# Gate_Drivers.net
KiCad netlist of a schematic drawn in Altium Designer
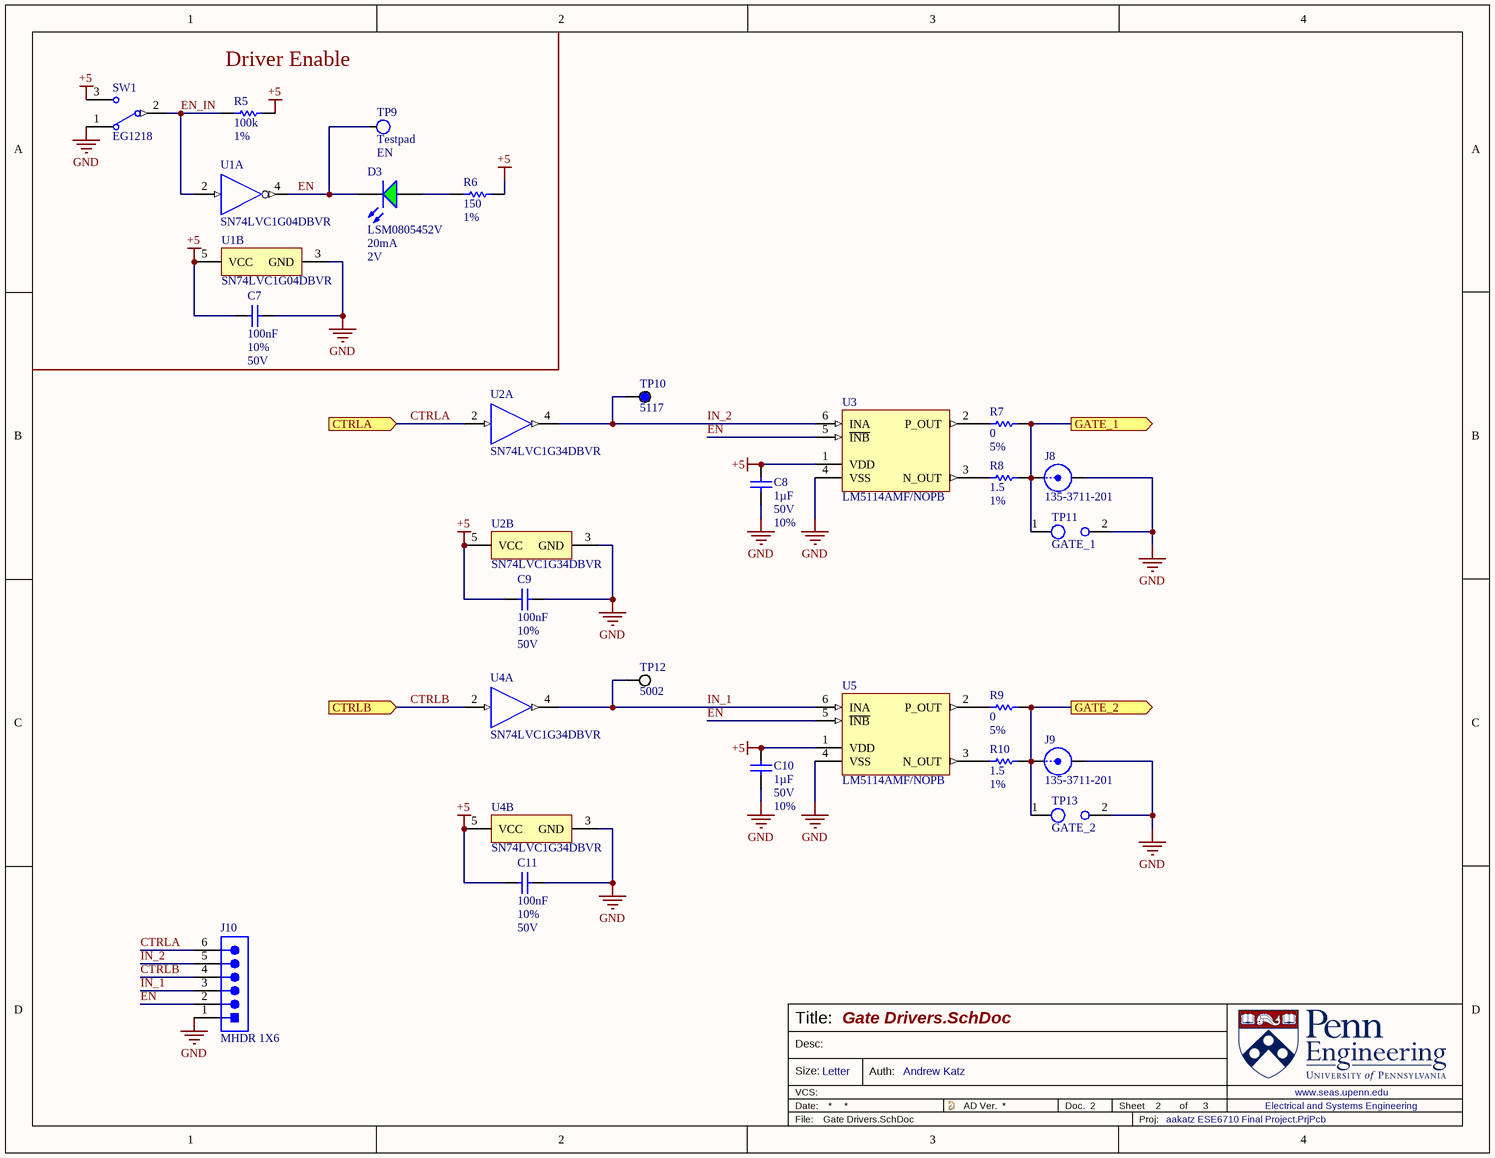
[diagram p0: Gate Drivers.SchDoc]

(export (version "E")
  (design (tool "Eeschema 10.0.6"))
  (components
    (comp (ref "C7")
      (value "100nF")
      (footprint "0805_CAP")
      (description "Capacitor Surface Mount 0805 Footprint 0.1UF 50V 10% Tolerance Ceramic X7R")
      (fields
        (field (name "TOLERANCE") "10%")
        (field (name "MANUFACTURER") "Various")
        (field (name "VOLTAGE") "50V")
        (field (name "Comment") "CAP 0805 0.1UF 50V 10% X7R")
      )
      (libsource (lib "University of Pennsylvania (ESE)") (part "cap"))
    )
    (comp (ref "C8")
      (value "1µF")
      (footprint "1206_CAP")
      (description "Capacitor Surface Mount 1206 Footprint 1.0UF 50V 10% Tolerance Ceramic X7R")
      (fields
        (field (name "VOLTAGE") "50V")
        (field (name "TOLERANCE") "10%")
        (field (name "MANUFACTURER") "Various")
        (field (name "Comment") "CAP 1206 1.0UF 50V 10% X7R")
      )
      (libsource (lib "University of Pennsylvania (ESE)") (part "cap"))
    )
    (comp (ref "C9")
      (value "100nF")
      (footprint "0805_CAP")
      (description "Capacitor Surface Mount 0805 Footprint 0.1UF 50V 10% Tolerance Ceramic X7R")
      (fields
        (field (name "TOLERANCE") "10%")
        (field (name "MANUFACTURER") "Various")
        (field (name "VOLTAGE") "50V")
        (field (name "Comment") "CAP 0805 0.1UF 50V 10% X7R")
      )
      (libsource (lib "University of Pennsylvania (ESE)") (part "cap"))
    )
    (comp (ref "C10")
      (value "1µF")
      (footprint "1206_CAP")
      (description "Capacitor Surface Mount 1206 Footprint 1.0UF 50V 10% Tolerance Ceramic X7R")
      (fields
        (field (name "VOLTAGE") "50V")
        (field (name "TOLERANCE") "10%")
        (field (name "MANUFACTURER") "Various")
        (field (name "Comment") "CAP 1206 1.0UF 50V 10% X7R")
      )
      (libsource (lib "University of Pennsylvania (ESE)") (part "cap"))
    )
    (comp (ref "C11")
      (value "100nF")
      (footprint "0805_CAP")
      (description "Capacitor Surface Mount 0805 Footprint 0.1UF 50V 10% Tolerance Ceramic X7R")
      (fields
        (field (name "TOLERANCE") "10%")
        (field (name "MANUFACTURER") "Various")
        (field (name "VOLTAGE") "50V")
        (field (name "Comment") "CAP 0805 0.1UF 50V 10% X7R")
      )
      (libsource (lib "University of Pennsylvania (ESE)") (part "cap"))
    )
    (comp (ref "D3")
      (value "LSM0805452V")
      (footprint "LED_0805")
      (description "Single Color LED, Green, 0805")
      (fields (field (name "CURRENT") "20mA") (field (name "FORWARD VOLTAGE") "2V"))
      (libsource (lib "University of Pennsylvania (ESE)") (part "LED-GREEN-AK-2"))
    )
    (comp (ref "J8")
      (value "135-3711-201")
      (footprint "135-3711-201-Vias-Footprint-1")
      (description "RF / Coaxial Connector, MMCX Coaxial, Straight Jack, Surface Mount Straight, 50 ohm")
      (libsource (lib "University of Pennsylvania (ESE)") (part "RF Connector"))
    )
    (comp (ref "J9")
      (value "135-3711-201")
      (footprint "135-3711-201-Vias-Footprint-1")
      (description "RF / Coaxial Connector, MMCX Coaxial, Straight Jack, Surface Mount Straight, 50 ohm")
      (libsource (lib "University of Pennsylvania (ESE)") (part "RF Connector"))
    )
    (comp (ref "J10")
      (value "MHDR 1X6")
      (footprint "MHDR 1X6")
      (description "Header, 6-Pin, 0.1in Pitch, Male")
      (fields (field (name "JLCPCB PART #") "C178289"))
      (libsource (lib "University of Pennsylvania (ESE)") (part "Header 1X6"))
    )
    (comp (ref "R5")
      (value "100k")
      (footprint "0805_RES")
      (description "Resistor Surface Mount, 100K Ohms, 0805 Footprint, 1% Tolerance 0.125W")
      (fields
        (field (name "MANUFACTURER") "Various")
        (field (name "TOLERANCE") "1%")
        (field (name "Comment") "RES 0805 100K 1%")
      )
      (libsource (lib "University of Pennsylvania (ESE)") (part "res"))
    )
    (comp (ref "R6")
      (value "150")
      (footprint "0805_RES")
      (description "Resistor Surface Mount, 150 Ohms, 0805 Footprint, 1% Tolerance 0.125W")
      (fields
        (field (name "MANUFACTURER") "Various")
        (field (name "TOLERANCE") "1%")
        (field (name "Comment") "RES 0805 150 1%")
      )
      (libsource (lib "University of Pennsylvania (ESE)") (part "res"))
    )
    (comp (ref "R7")
      (value "0")
      (footprint "0603_RES")
      (description "Resistor Surface Mount, 0 Ohms, 0603 Footprint, 5% Tolerance 0.1W")
      (fields
        (field (name "JLCPCB PART #") "C21189")
        (field (name "TOLERANCE") "5%")
        (field (name "MANUFACTURER") "Various")
      )
      (libsource (lib "University of Pennsylvania (ESE)") (part "res"))
    )
    (comp (ref "R8")
      (value "1.5")
      (footprint "0603_RES")
      (description "Resistor Surface Mount, 1.5 Ohms, 0603 Footprint, 1% Tolerance 0.1W")
      (fields
        (field (name "TOLERANCE") "1%")
        (field (name "MANUFACTURER") "Various")
        (field (name "Comment") "RES 0603 1.5 1%")
      )
      (libsource (lib "University of Pennsylvania (ESE)") (part "res"))
    )
    (comp (ref "R9")
      (value "0")
      (footprint "0603_RES")
      (description "Resistor Surface Mount, 0 Ohms, 0603 Footprint, 5% Tolerance 0.1W")
      (fields
        (field (name "JLCPCB PART #") "C21189")
        (field (name "TOLERANCE") "5%")
        (field (name "MANUFACTURER") "Various")
      )
      (libsource (lib "University of Pennsylvania (ESE)") (part "res"))
    )
    (comp (ref "R10")
      (value "1.5")
      (footprint "0603_RES")
      (description "Resistor Surface Mount, 1.5 Ohms, 0603 Footprint, 1% Tolerance 0.1W")
      (fields
        (field (name "TOLERANCE") "1%")
        (field (name "MANUFACTURER") "Various")
        (field (name "Comment") "RES 0603 1.5 1%")
      )
      (libsource (lib "University of Pennsylvania (ESE)") (part "res"))
    )
    (comp (ref "SW1")
      (value "EG1218")
      (footprint "ESWI-EG1218_V")
      (libsource (lib "University of Pennsylvania (ESE)") (part "SW-SPDT-3_B"))
    )
    (comp (ref "TP9")
      (value "Testpad")
      (footprint "Test PTH 15-30")
      (description "Test Pad/Point (Testpoint, Testpad), for probing")
      (fields (field (name "NETNAME") "EN"))
      (libsource (lib "University of Pennsylvania (ESE)") (part "Test Pad"))
    )
    (comp (ref "TP10")
      (value "5117")
      (footprint "KSTN-5117")
      (description "Test Point, Blue, 1-Pin THD, RoHS, Bulk")
      (fields (field (name "MANUFACTURER") "KeystoneElectronics"))
      (libsource (lib "University of Pennsylvania (ESE)") (part "5117"))
    )
    (comp (ref "TP11")
      (value "Test Point - Scope with Ground Spring (No Socket)")
      (footprint "No Silk Test Point - Scope with Ground Spring-Footprint-1")
      (fields (field (name "NETNAME") "GATE_1"))
      (libsource (lib "University of Pennsylvania (ESE)") (part "Test Pad with Ground (No BOM)"))
    )
    (comp (ref "TP12")
      (value "5002")
      (footprint "KSTN-5002")
      (description "Test Point, White, 1-Pin THD, RoHS, Bulk")
      (fields (field (name "MANUFACTURER") "KeystoneElectronics"))
      (libsource (lib "University of Pennsylvania (ESE)") (part "5002"))
    )
    (comp (ref "TP13")
      (value "Test Point - Scope with Ground Spring (No Socket)")
      (footprint "No Silk Test Point - Scope with Ground Spring-Footprint-1")
      (fields (field (name "NETNAME") "GATE_2"))
      (libsource (lib "University of Pennsylvania (ESE)") (part "Test Pad with Ground (No BOM)"))
    )
    (comp (ref "U1")
      (value "SN74LVC1G04DBVR")
      (footprint "DBV0005A_N")
      (description "SINGLE INVERTER GATE Inverter, LVC/LCX/Z Series, 1-Func, 1-Input, CMOS, PDSO5")
      (libsource (lib "University of Pennsylvania (ESE)") (part "TI-SN74XXX1XXX-XX-5_INV"))
    )
    (comp (ref "U2")
      (value "SN74LVC1G34DBVR")
      (footprint "DBV0005A_N")
      (description "1 32mA 1.65V~5.5V 32mA 1 SOT-23-5 Buffer/Driver/Transceiver ROHS")
      (libsource (lib "University of Pennsylvania (ESE)") (part "Copy of TI-SN74XXX1XXX-XX-5"))
    )
    (comp (ref "U3")
      (value "LM5114AMF/NOPB")
      (footprint "DBV0006A_N")
      (description "7.6-A/1.3-A single channel gate driver with 4-V UVLO and split outputs 6-SOT-23 -40 to 125")
      (libsource (lib "University of Pennsylvania (ESE)") (part "LM5114AMF_NOPB-Symbol-1"))
    )
    (comp (ref "U4")
      (value "SN74LVC1G34DBVR")
      (footprint "DBV0005A_N")
      (description "1 32mA 1.65V~5.5V 32mA 1 SOT-23-5 Buffer/Driver/Transceiver ROHS")
      (libsource (lib "University of Pennsylvania (ESE)") (part "Copy of TI-SN74XXX1XXX-XX-5"))
    )
    (comp (ref "U5")
      (value "LM5114AMF/NOPB")
      (footprint "DBV0006A_N")
      (description "7.6-A/1.3-A single channel gate driver with 4-V UVLO and split outputs 6-SOT-23 -40 to 125")
      (libsource (lib "University of Pennsylvania (ESE)") (part "LM5114AMF_NOPB-Symbol-1"))
    )
  )
  (nets
    (net (code "1") (name "+5") (class "Default")
      (node (ref "C10") (pin "2") (pinfunction "2_2") (pintype "passive"))
      (node (ref "C11") (pin "1") (pinfunction "1_1") (pintype "passive"))
      (node (ref "C7") (pin "1") (pinfunction "1_1") (pintype "passive"))
      (node (ref "C8") (pin "2") (pinfunction "2_2") (pintype "passive"))
      (node (ref "C9") (pin "1") (pinfunction "1_1") (pintype "passive"))
      (node (ref "R5") (pin "2") (pinfunction "2_2") (pintype "passive"))
      (node (ref "R6") (pin "2") (pinfunction "2_2") (pintype "passive"))
      (node (ref "SW1") (pin "3") (pinfunction "3_3") (pintype "passive"))
      (node (ref "U1") (pin "5") (pinfunction "VCC_5") (pintype "power_in"))
      (node (ref "U2") (pin "5") (pinfunction "VCC_5") (pintype "power_in"))
      (node (ref "U3") (pin "1") (pinfunction "VDD_1") (pintype "power_in"))
      (node (ref "U4") (pin "5") (pinfunction "VCC_5") (pintype "power_in"))
      (node (ref "U5") (pin "1") (pinfunction "VDD_1") (pintype "power_in"))
    )
    (net (code "2") (name "/CTRLA") (class "Default")
      (node (ref "J10") (pin "6") (pinfunction "6_6") (pintype "passive"))
      (node (ref "U2") (pin "2") (pinfunction "A_2") (pintype "input"))
    )
    (net (code "3") (name "/CTRLB") (class "Default")
      (node (ref "J10") (pin "4") (pinfunction "4_4") (pintype "passive"))
      (node (ref "U4") (pin "2") (pinfunction "A_2") (pintype "input"))
    )
    (net (code "4") (name "/EN") (class "Default")
      (node (ref "D3") (pin "K") (pinfunction "K_K") (pintype "passive"))
      (node (ref "J10") (pin "2") (pinfunction "2_2") (pintype "passive"))
      (node (ref "TP9") (pin "1") (pinfunction "1_1") (pintype "passive"))
      (node (ref "U1") (pin "4") (pinfunction "Y_4") (pintype "output"))
      (node (ref "U3") (pin "5") (pinfunction "INB_5") (pintype "input"))
      (node (ref "U5") (pin "5") (pinfunction "INB_5") (pintype "input"))
    )
    (net (code "5") (name "/EN_IN") (class "Default")
      (node (ref "R5") (pin "1") (pinfunction "1_1") (pintype "passive"))
      (node (ref "SW1") (pin "2") (pinfunction "COM_2") (pintype "output"))
      (node (ref "U1") (pin "2") (pinfunction "A_2") (pintype "input"))
    )
    (net (code "6") (name "/GATE_1") (class "Default")
      (node (ref "J8") (pin "1") (pinfunction "1_1") (pintype "passive"))
      (node (ref "R7") (pin "2") (pinfunction "2_2") (pintype "passive"))
      (node (ref "R8") (pin "2") (pinfunction "2_2") (pintype "passive"))
      (node (ref "TP11") (pin "1") (pinfunction "Signal_1") (pintype "passive"))
    )
    (net (code "7") (name "/GATE_2") (class "Default")
      (node (ref "J9") (pin "1") (pinfunction "1_1") (pintype "passive"))
      (node (ref "R10") (pin "2") (pinfunction "2_2") (pintype "passive"))
      (node (ref "R9") (pin "2") (pinfunction "2_2") (pintype "passive"))
      (node (ref "TP13") (pin "1") (pinfunction "Signal_1") (pintype "passive"))
    )
    (net (code "8") (name "/IN_1") (class "Default")
      (node (ref "J10") (pin "3") (pinfunction "3_3") (pintype "passive"))
      (node (ref "TP12") (pin "1") (pintype "passive"))
      (node (ref "U4") (pin "4") (pinfunction "Y_4") (pintype "output"))
      (node (ref "U5") (pin "6") (pinfunction "INA_6") (pintype "input"))
    )
    (net (code "9") (name "/IN_2") (class "Default")
      (node (ref "J10") (pin "5") (pinfunction "5_5") (pintype "passive"))
      (node (ref "TP10") (pin "1") (pintype "passive"))
      (node (ref "U2") (pin "4") (pinfunction "Y_4") (pintype "output"))
      (node (ref "U3") (pin "6") (pinfunction "INA_6") (pintype "input"))
    )
    (net (code "10") (name "GND") (class "Default")
      (node (ref "C10") (pin "1") (pinfunction "1_1") (pintype "passive"))
      (node (ref "C11") (pin "2") (pinfunction "2_2") (pintype "passive"))
      (node (ref "C7") (pin "2") (pinfunction "2_2") (pintype "passive"))
      (node (ref "C8") (pin "1") (pinfunction "1_1") (pintype "passive"))
      (node (ref "C9") (pin "2") (pinfunction "2_2") (pintype "passive"))
      (node (ref "J10") (pin "1") (pinfunction "1_1") (pintype "passive"))
      (node (ref "J8") (pin "2") (pinfunction "SHELL_2") (pintype "passive"))
      (node (ref "J9") (pin "2") (pinfunction "SHELL_2") (pintype "passive"))
      (node (ref "SW1") (pin "1") (pinfunction "1_1") (pintype "passive"))
      (node (ref "TP11") (pin "2") (pinfunction "GND_2") (pintype "passive"))
      (node (ref "TP13") (pin "2") (pinfunction "GND_2") (pintype "passive"))
      (node (ref "U1") (pin "3") (pinfunction "GND_3") (pintype "power_in"))
      (node (ref "U2") (pin "3") (pinfunction "GND_3") (pintype "power_in"))
      (node (ref "U3") (pin "4") (pinfunction "VSS_4") (pintype "power_in"))
      (node (ref "U4") (pin "3") (pinfunction "GND_3") (pintype "power_in"))
      (node (ref "U5") (pin "4") (pinfunction "VSS_4") (pintype "power_in"))
    )
    (net (code "11") (name "Net-(D3-PadA)") (class "Default")
      (node (ref "D3") (pin "A") (pinfunction "A_A") (pintype "passive"))
      (node (ref "R6") (pin "1") (pinfunction "1_1") (pintype "passive"))
    )
    (net (code "12") (name "Net-(U3-N_OUT)") (class "Default")
      (node (ref "R8") (pin "1") (pinfunction "1_1") (pintype "passive"))
      (node (ref "U3") (pin "3") (pinfunction "N_OUT_3") (pintype "output"))
    )
    (net (code "13") (name "Net-(U3-P_OUT)") (class "Default")
      (node (ref "R7") (pin "1") (pinfunction "1_1") (pintype "passive"))
      (node (ref "U3") (pin "2") (pinfunction "P_OUT_2") (pintype "output"))
    )
    (net (code "14") (name "Net-(U5-N_OUT)") (class "Default")
      (node (ref "R10") (pin "1") (pinfunction "1_1") (pintype "passive"))
      (node (ref "U5") (pin "3") (pinfunction "N_OUT_3") (pintype "output"))
    )
    (net (code "15") (name "Net-(U5-P_OUT)") (class "Default")
      (node (ref "R9") (pin "1") (pinfunction "1_1") (pintype "passive"))
      (node (ref "U5") (pin "2") (pinfunction "P_OUT_2") (pintype "output"))
    )
    (net (code "16") (name "unconnected-(U1B-NC-Pad1)") (class "Default")
      (node (ref "U1") (pin "1") (pinfunction "NC_1") (pintype "passive"))
    )
    (net (code "17") (name "unconnected-(U2B-NC-Pad1)") (class "Default")
      (node (ref "U2") (pin "1") (pinfunction "NC_1") (pintype "passive"))
    )
    (net (code "18") (name "unconnected-(U4B-NC-Pad1)") (class "Default")
      (node (ref "U4") (pin "1") (pinfunction "NC_1") (pintype "passive"))
    )
  )
)
